# receiver.net
KiCad netlist of a schematic drawn in EAGLE
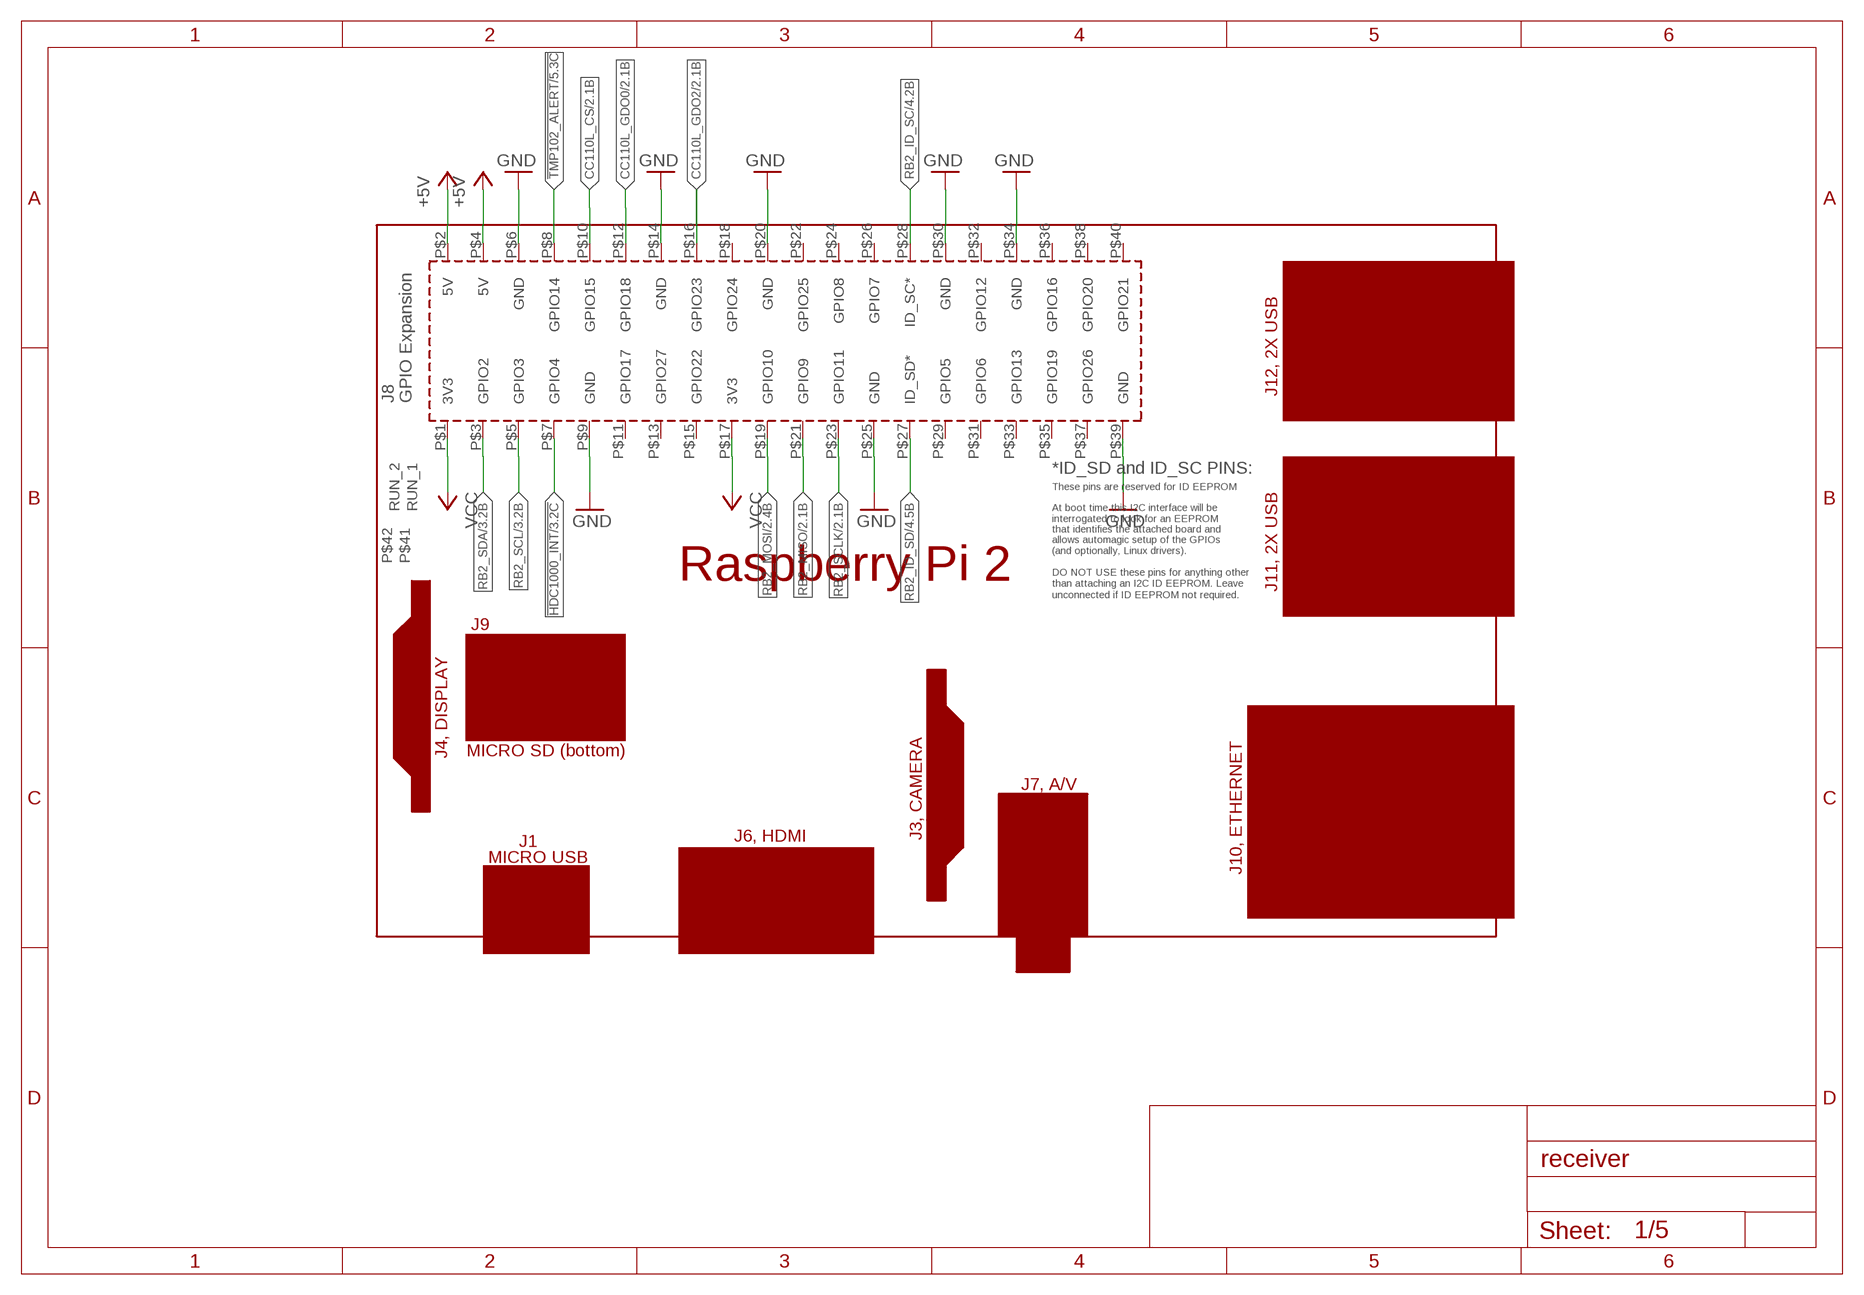
[diagram p0: schematic, sheet 1]
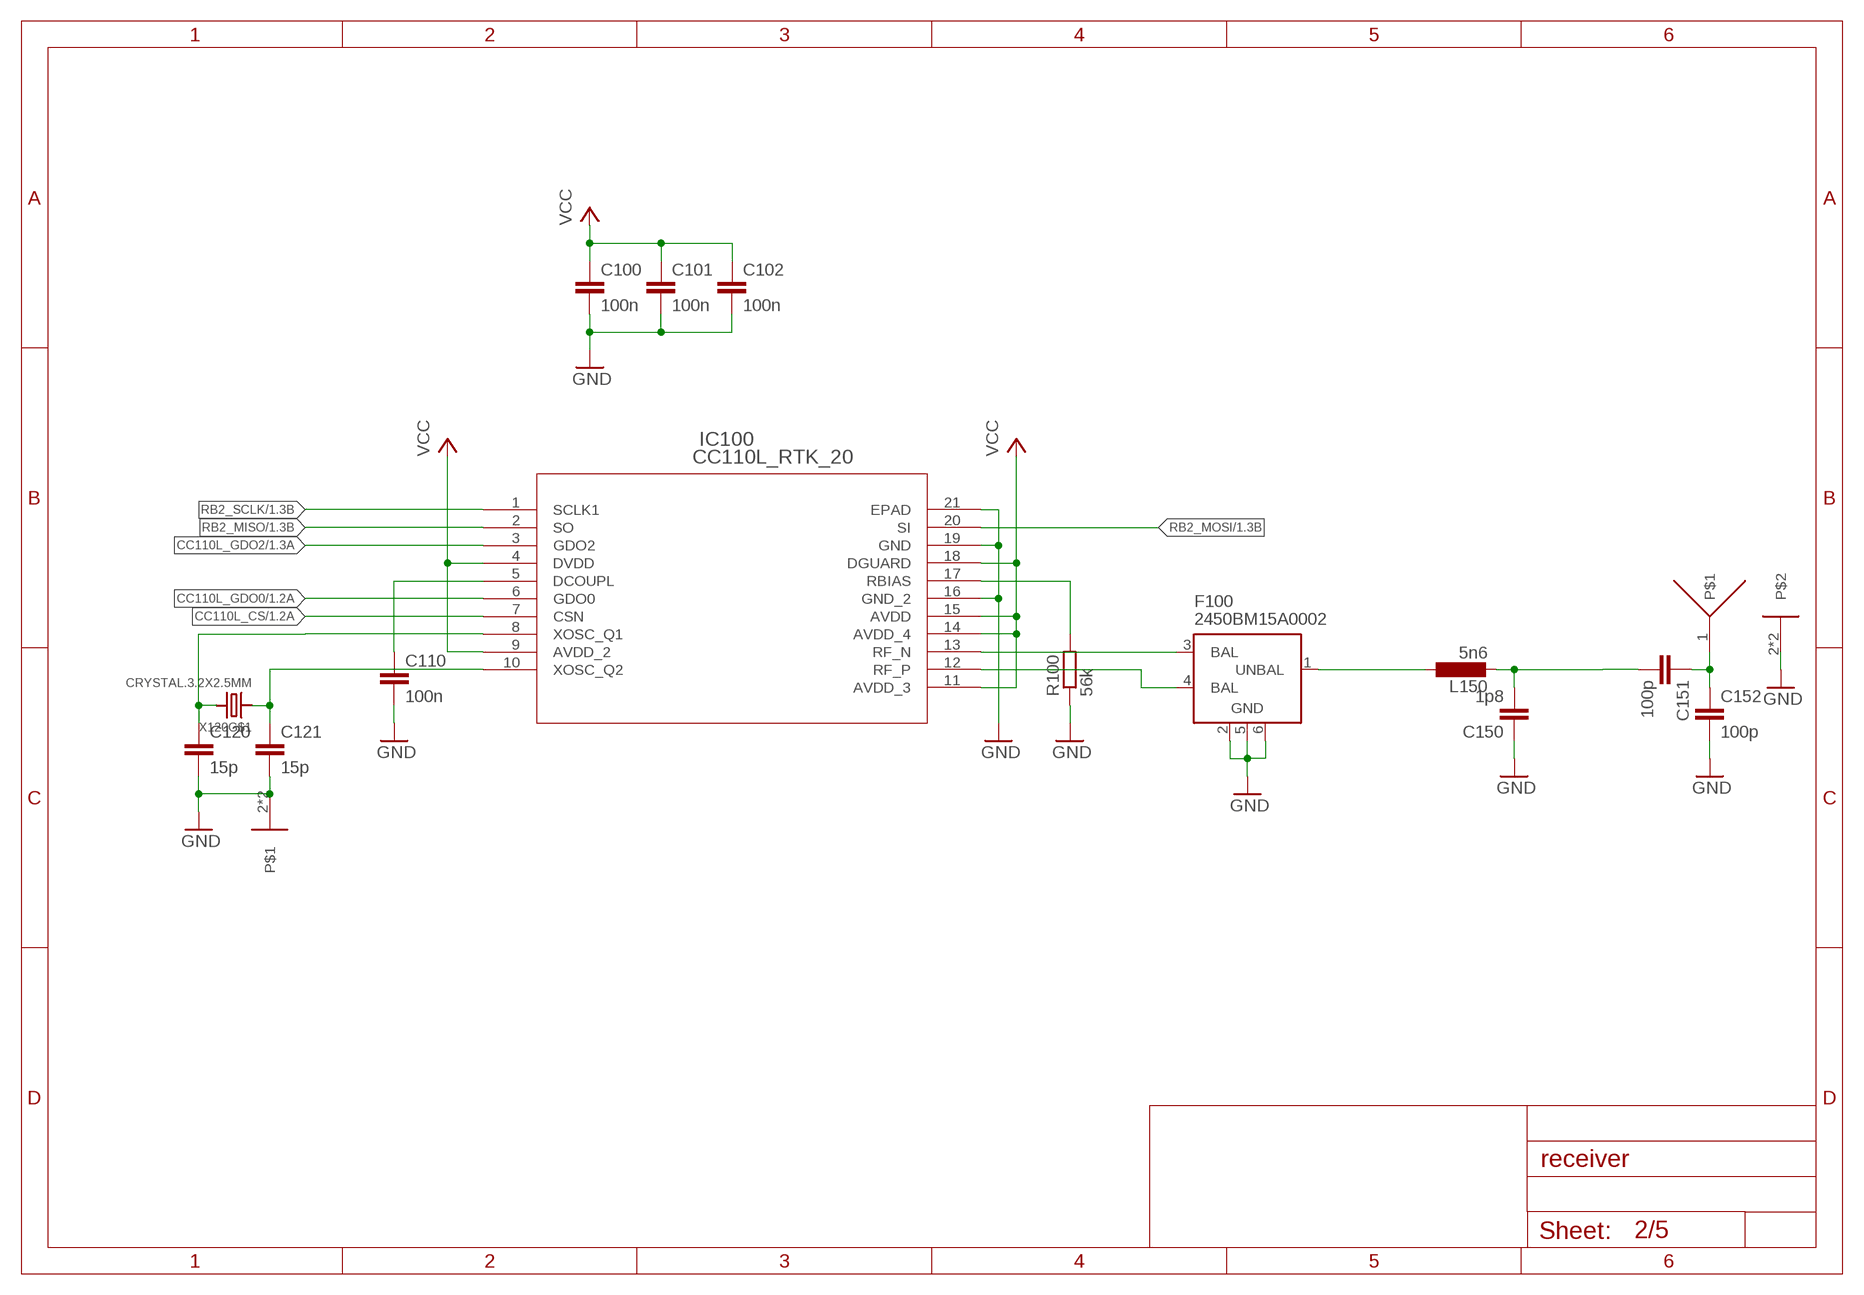
[diagram p1: schematic, sheet 2]
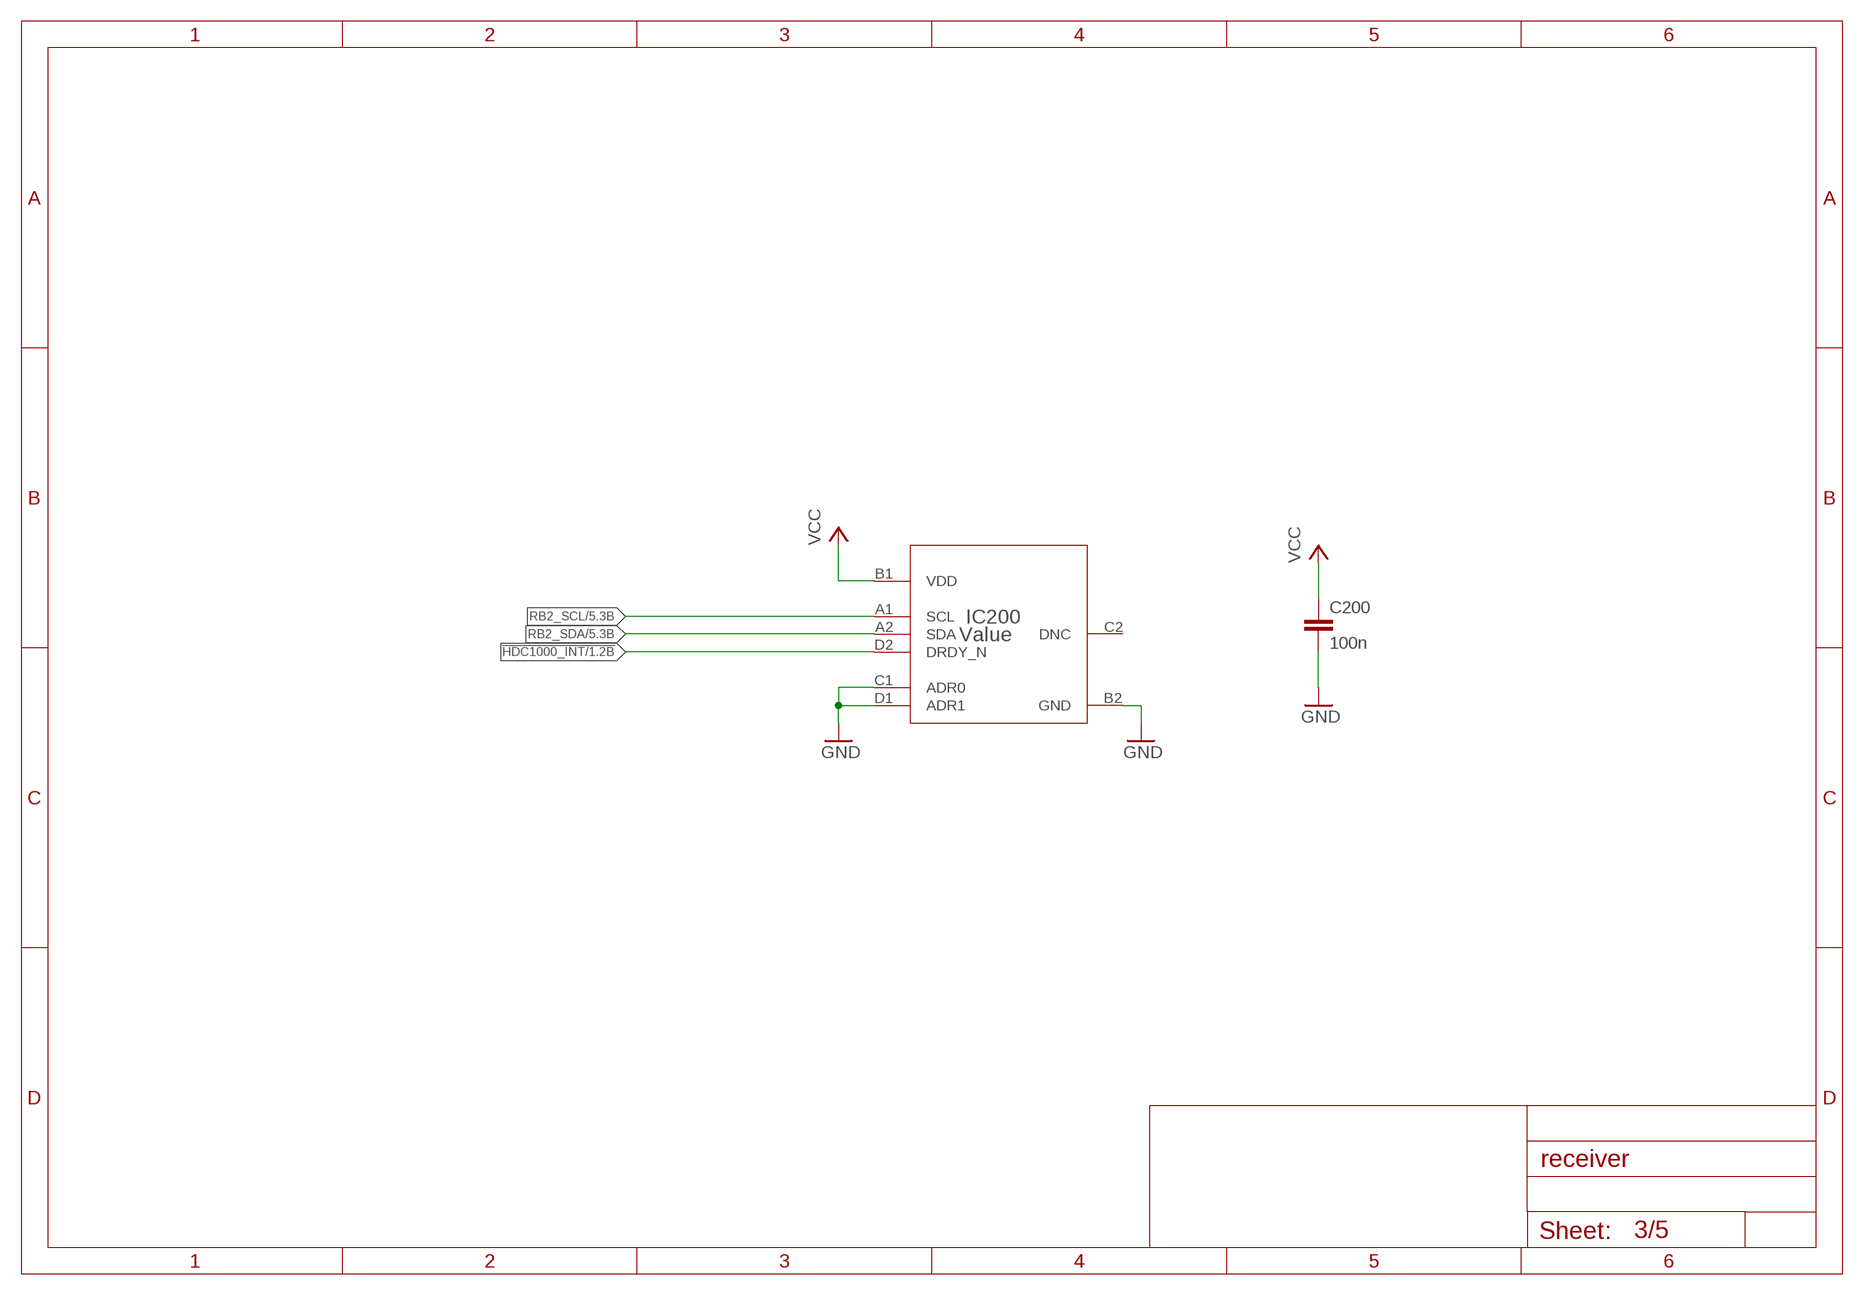
[diagram p2: schematic, sheet 3]
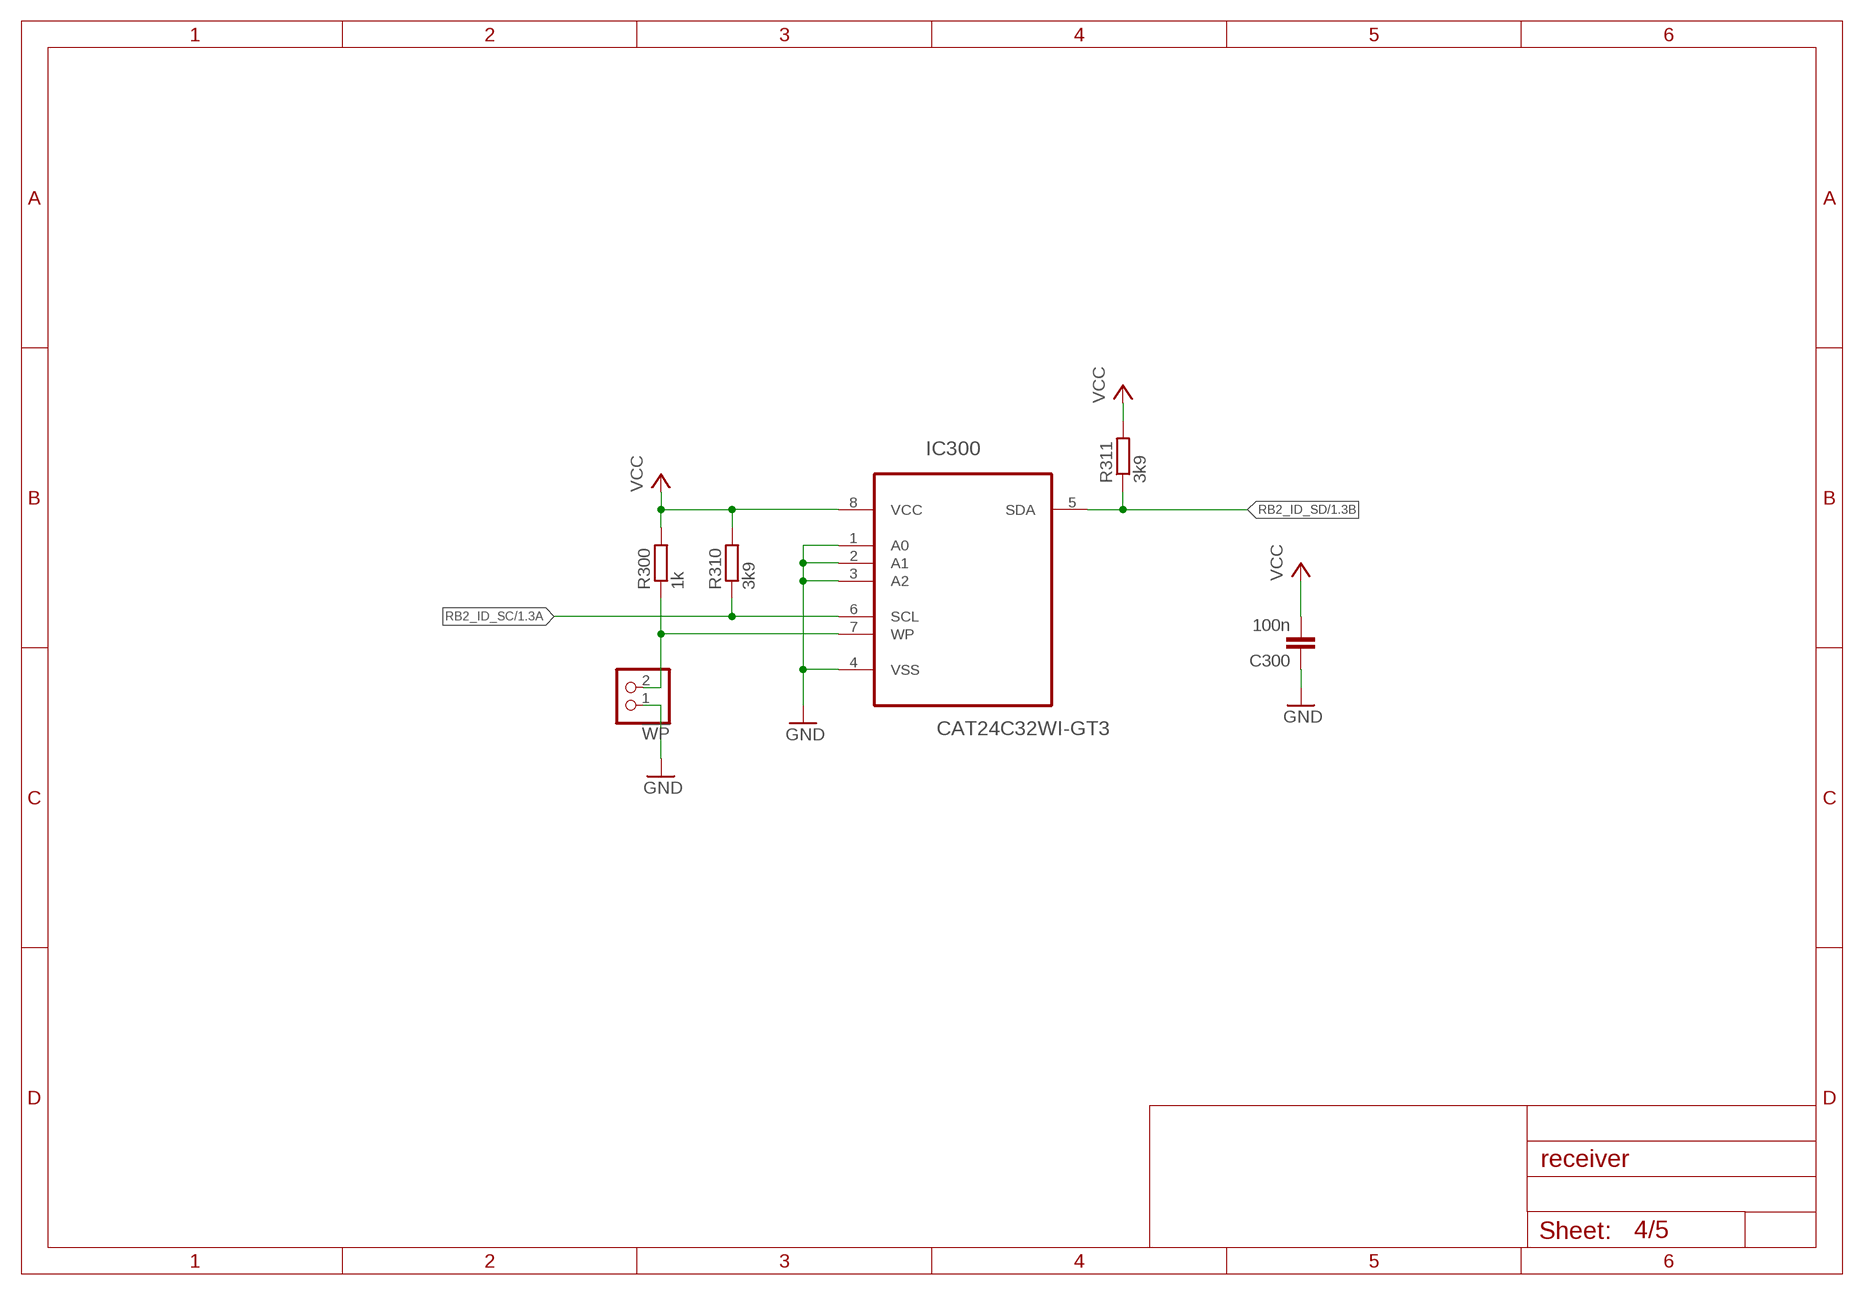
[diagram p3: schematic, sheet 4]
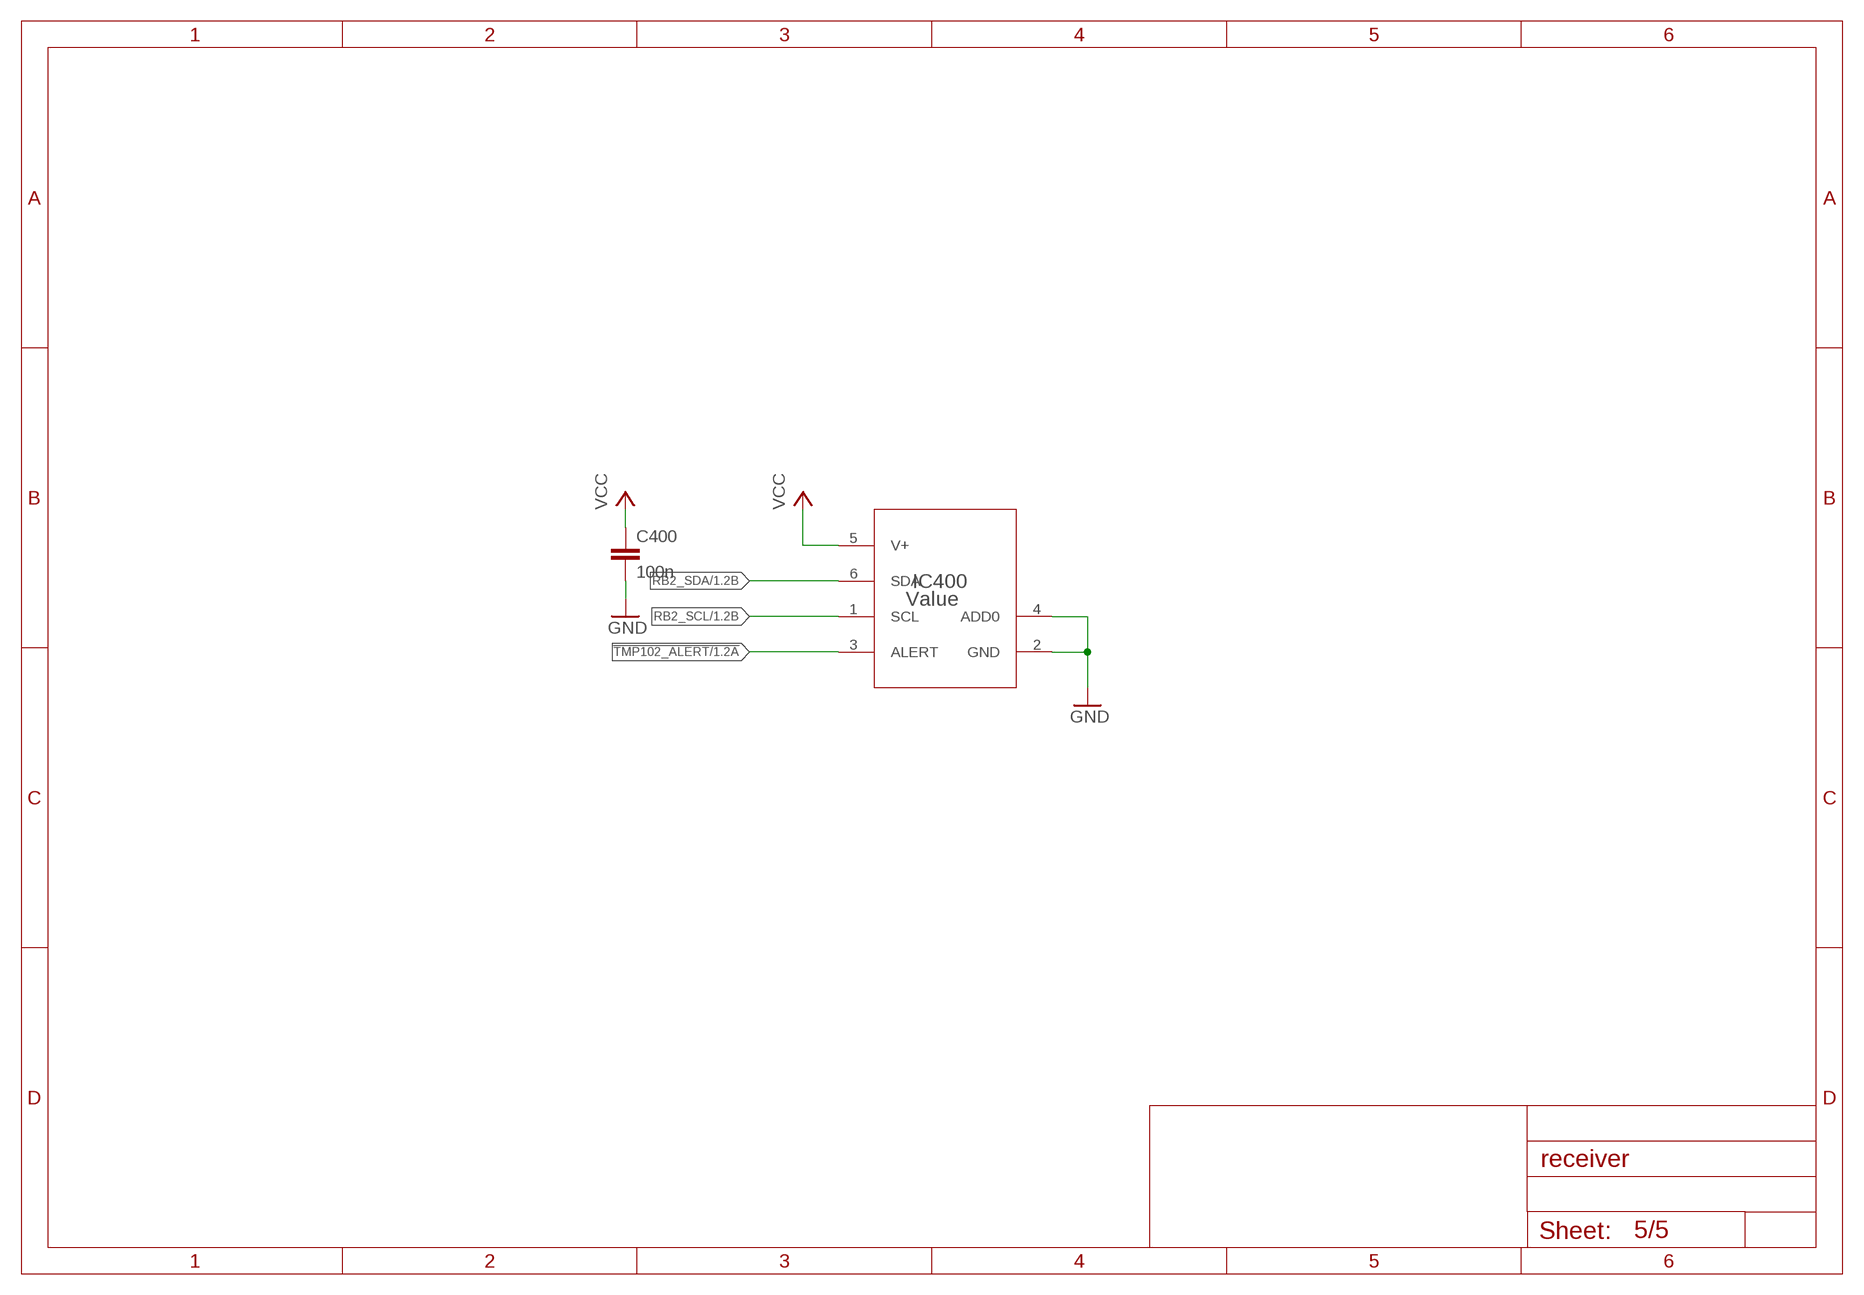
[diagram p4: schematic, sheet 5]

(export (version "E")
  (design (tool "Eeschema 10.0.6"))
  (components
    (comp (ref "C200")
      (value "100n")
      (footprint "eagle-import:C0603")
      (libsource (lib "eagle-import") (part "C-EUC0603"))
    )
    (comp (ref "IC200")
      (value "Value")
      (footprint "eagle-import:YPA0008AGAE")
      (fields
        (field (name "ALTERNATEPARTNUMBER") "HDC1000YPAT")
        (field (name "MANUFACTURER") "Texas Instruments")
        (field (name "PARTNUMBER") "HDC1000YPAR")
      )
      (libsource (lib "eagle-import") (part "HDC1000YPAR"))
    )
    (comp (ref "C100")
      (value "100n")
      (footprint "eagle-import:C0603")
      (libsource (lib "eagle-import") (part "C-EUC0603"))
    )
    (comp (ref "C101")
      (value "100n")
      (footprint "eagle-import:C0603")
      (libsource (lib "eagle-import") (part "C-EUC0603"))
    )
    (comp (ref "C102")
      (value "100n")
      (footprint "eagle-import:C0603")
      (libsource (lib "eagle-import") (part "C-EUC0603"))
    )
    (comp (ref "C110")
      (value "100n")
      (footprint "eagle-import:C0603")
      (libsource (lib "eagle-import") (part "C-EUC0603"))
    )
    (comp (ref "C120")
      (value "15p")
      (footprint "eagle-import:C0603")
      (libsource (lib "eagle-import") (part "C-EUC0603"))
    )
    (comp (ref "C121")
      (value "15p")
      (footprint "eagle-import:C0603")
      (libsource (lib "eagle-import") (part "C-EUC0603"))
    )
    (comp (ref "C150")
      (value "1p8")
      (footprint "eagle-import:C0603K")
      (libsource (lib "eagle-import") (part "C-EUC0603K"))
    )
    (comp (ref "C151")
      (value "100p")
      (footprint "eagle-import:C0603")
      (libsource (lib "eagle-import") (part "C-EUC0603"))
    )
    (comp (ref "C152")
      (value "100p")
      (footprint "eagle-import:C0603K")
      (libsource (lib "eagle-import") (part "C-EUC0603K"))
    )
    (comp (ref "F100")
      (value "2450BM15A0002")
      (footprint "eagle-import:2450BM15A0002")
      (libsource (lib "eagle-import") (part "2450BM15A0002"))
    )
    (comp (ref "IC100")
      (value "CC110L_RTK_20")
      (footprint "eagle-import:RTK20_2P4X2P4")
      (fields (field (name "GENERIC_PART_NUMBER") "CC110L") (field (name "MANUFACTURER") "Texas Instruments"))
      (libsource (lib "eagle-import") (part "CC110L_RTK_20"))
    )
    (comp (ref "L150")
      (value "5n6")
      (footprint "eagle-import:L2012C")
      (libsource (lib "eagle-import") (part "L-EUL2012C"))
    )
    (comp (ref "R100")
      (value "56k")
      (footprint "eagle-import:R0603")
      (libsource (lib "eagle-import") (part "R-EU_R0603"))
    )
    (comp (ref "U$1")
      (value "ANTENNA868W3013-INV")
      (footprint "eagle-import:W3013-INV")
      (libsource (lib "eagle-import") (part "ANTENNA868W3013-INV"))
    )
    (comp (ref "X120")
      (value "CRYSTAL.3.2X2.5MM")
      (footprint "eagle-import:3.2X2.5MM")
      (libsource (lib "eagle-import") (part "CRYSTAL.3.2X2.5MM"))
    )
    (comp (ref "C400")
      (value "100n")
      (footprint "eagle-import:C0603")
      (libsource (lib "eagle-import") (part "C-EUC0603"))
    )
    (comp (ref "IC400")
      (value "Value")
      (footprint "eagle-import:DRL0006A")
      (fields (field (name "MANUFACTURER") "Texas Instruments") (field (name "PARTNUMBER") "TMP102AQDRLRQ1"))
      (libsource (lib "eagle-import") (part "TMP102AQDRLRQ1"))
    )
    (comp (ref "!WP")
      (value "PINHD-1X2")
      (footprint "eagle-import:1X02")
      (libsource (lib "eagle-import") (part "PINHD-1X2"))
    )
    (comp (ref "C300")
      (value "100n")
      (footprint "eagle-import:C0603")
      (libsource (lib "eagle-import") (part "C-EUC0603"))
    )
    (comp (ref "IC300")
      (value "CAT24C32WI-GT3")
      (footprint "eagle-import:SOIC127P600X175-8N")
      (libsource (lib "eagle-import") (part "CAT24C32WI-GT3"))
    )
    (comp (ref "R300")
      (value "1k")
      (footprint "eagle-import:R0603")
      (libsource (lib "eagle-import") (part "R-EU_R0603"))
    )
    (comp (ref "R310")
      (value "3k9")
      (footprint "eagle-import:R0603")
      (libsource (lib "eagle-import") (part "R-EU_R0603"))
    )
    (comp (ref "R311")
      (value "3k9")
      (footprint "eagle-import:R0603")
      (libsource (lib "eagle-import") (part "R-EU_R0603"))
    )
    (comp (ref "PCB1")
      (value "RPI2")
      (footprint "eagle-import:RPI2")
      (libsource (lib "eagle-import") (part "RPI2"))
    )
  )
  (nets
    (net (code "1") (name "+5V") (class "Default")
      (node (ref "PCB1") (pin "P$2") (pinfunction "5V_P$2") (pintype "bidirectional"))
      (node (ref "PCB1") (pin "P$4") (pinfunction "5V_P$4") (pintype "bidirectional"))
    )
    (net (code "2") (name "CC110L_CS") (class "Default")
      (node (ref "IC100") (pin "7") (pinfunction "CSN_7") (pintype "passive"))
      (node (ref "PCB1") (pin "P$10") (pinfunction "GPIO15_P$10") (pintype "bidirectional"))
    )
    (net (code "3") (name "CC110L_GDO0") (class "Default")
      (node (ref "IC100") (pin "6") (pinfunction "GDO0_6") (pintype "output"))
      (node (ref "PCB1") (pin "P$12") (pinfunction "GPIO18_P$12") (pintype "bidirectional"))
    )
    (net (code "4") (name "CC110L_GDO2") (class "Default")
      (node (ref "IC100") (pin "3") (pinfunction "GDO2_3") (pintype "output"))
      (node (ref "PCB1") (pin "P$16") (pinfunction "GPIO23_P$16") (pintype "bidirectional"))
    )
    (net (code "5") (name "GND") (class "Default")
      (node (ref "!WP") (pin "1") (pinfunction "1_1") (pintype "passive"))
      (node (ref "C100") (pin "2") (pinfunction "2_2") (pintype "passive"))
      (node (ref "C101") (pin "2") (pinfunction "2_2") (pintype "passive"))
      (node (ref "C102") (pin "2") (pinfunction "2_2") (pintype "passive"))
      (node (ref "C110") (pin "2") (pinfunction "2_2") (pintype "passive"))
      (node (ref "C120") (pin "2") (pinfunction "2_2") (pintype "passive"))
      (node (ref "C121") (pin "2") (pinfunction "2_2") (pintype "passive"))
      (node (ref "C150") (pin "1") (pinfunction "1_1") (pintype "passive"))
      (node (ref "C152") (pin "2") (pinfunction "2_2") (pintype "passive"))
      (node (ref "C200") (pin "2") (pinfunction "2_2") (pintype "passive"))
      (node (ref "C300") (pin "1") (pinfunction "1_1") (pintype "passive"))
      (node (ref "C400") (pin "2") (pinfunction "2_2") (pintype "passive"))
      (node (ref "F100") (pin "2") (pinfunction "GND_2") (pintype "passive"))
      (node (ref "F100") (pin "5") (pinfunction "GND_5") (pintype "passive"))
      (node (ref "F100") (pin "6") (pinfunction "GND_6") (pintype "passive"))
      (node (ref "IC100") (pin "16") (pinfunction "GND_2_16") (pintype "power_in"))
      (node (ref "IC100") (pin "19") (pinfunction "GND_19") (pintype "power_in"))
      (node (ref "IC100") (pin "21") (pinfunction "EPAD_21") (pintype "power_in"))
      (node (ref "IC200") (pin "B2") (pinfunction "GND_B2") (pintype "power_in"))
      (node (ref "IC200") (pin "C1") (pinfunction "ADR0_C1") (pintype "input"))
      (node (ref "IC200") (pin "D1") (pinfunction "ADR1_D1") (pintype "input"))
      (node (ref "IC300") (pin "1") (pinfunction "A0_1") (pintype "input"))
      (node (ref "IC300") (pin "2") (pinfunction "A1_2") (pintype "input"))
      (node (ref "IC300") (pin "3") (pinfunction "A2_3") (pintype "input"))
      (node (ref "IC300") (pin "4") (pinfunction "VSS_4") (pintype "passive"))
      (node (ref "IC400") (pin "2") (pinfunction "GND_2") (pintype "power_in"))
      (node (ref "IC400") (pin "4") (pinfunction "ADD0_4") (pintype "input"))
      (node (ref "PCB1") (pin "P$14") (pinfunction "GND_P$14") (pintype "bidirectional"))
      (node (ref "PCB1") (pin "P$20") (pinfunction "GND_P$20") (pintype "bidirectional"))
      (node (ref "PCB1") (pin "P$25") (pinfunction "GND_P$25") (pintype "bidirectional"))
      (node (ref "PCB1") (pin "P$30") (pinfunction "GND_P$30") (pintype "bidirectional"))
      (node (ref "PCB1") (pin "P$34") (pinfunction "GND_P$34") (pintype "bidirectional"))
      (node (ref "PCB1") (pin "P$39") (pinfunction "GND_P$39") (pintype "bidirectional"))
      (node (ref "PCB1") (pin "P$6") (pinfunction "GND_P$6") (pintype "bidirectional"))
      (node (ref "PCB1") (pin "P$9") (pinfunction "GND_P$9") (pintype "bidirectional"))
      (node (ref "R100") (pin "1") (pinfunction "1_1") (pintype "passive"))
      (node (ref "U$1") (pin "2") (pinfunction "P$2_2") (pintype "bidirectional"))
      (node (ref "U$1") (pin "3") (pinfunction "P$2_3") (pintype "bidirectional"))
      (node (ref "X120") (pin "2") (pinfunction "P$1_2") (pintype "bidirectional"))
      (node (ref "X120") (pin "4") (pinfunction "P$1_4") (pintype "bidirectional"))
    )
    (net (code "6") (name "Net-(C150-Pad2)") (class "Default")
      (node (ref "C150") (pin "2") (pinfunction "2_2") (pintype "passive"))
      (node (ref "C151") (pin "2") (pinfunction "2_2") (pintype "passive"))
      (node (ref "L150") (pin "2") (pinfunction "2_2") (pintype "passive"))
    )
    (net (code "7") (name "Net-(F100-UNBAL)") (class "Default")
      (node (ref "F100") (pin "1") (pinfunction "UNBAL_1") (pintype "passive"))
      (node (ref "L150") (pin "1") (pinfunction "1_1") (pintype "passive"))
    )
    (net (code "8") (name "Net-(IC100-DCOUPL)") (class "Default")
      (node (ref "C110") (pin "1") (pinfunction "1_1") (pintype "passive"))
      (node (ref "IC100") (pin "5") (pinfunction "DCOUPL_5") (pintype "passive"))
    )
    (net (code "9") (name "Net-(IC100-RBIAS)") (class "Default")
      (node (ref "IC100") (pin "17") (pinfunction "RBIAS_17") (pintype "passive"))
      (node (ref "R100") (pin "2") (pinfunction "2_2") (pintype "passive"))
    )
    (net (code "10") (name "Net-(IC100-RF_N)") (class "Default")
      (node (ref "F100") (pin "3") (pinfunction "BAL_3") (pintype "passive"))
      (node (ref "IC100") (pin "13") (pinfunction "RF_N_13") (pintype "passive"))
    )
    (net (code "11") (name "Net-(IC100-RF_P)") (class "Default")
      (node (ref "F100") (pin "4") (pinfunction "BAL_4") (pintype "passive"))
      (node (ref "IC100") (pin "12") (pinfunction "RF_P_12") (pintype "passive"))
    )
    (net (code "12") (name "Net-(IC100-XOSC_Q1)") (class "Default")
      (node (ref "C120") (pin "1") (pinfunction "1_1") (pintype "passive"))
      (node (ref "IC100") (pin "8") (pinfunction "XOSC_Q1_8") (pintype "passive"))
      (node (ref "X120") (pin "3") (pinfunction "2_3") (pintype "passive"))
    )
    (net (code "13") (name "Net-(IC100-XOSC_Q2)") (class "Default")
      (node (ref "C121") (pin "1") (pinfunction "1_1") (pintype "passive"))
      (node (ref "IC100") (pin "10") (pinfunction "XOSC_Q2_10") (pintype "passive"))
      (node (ref "X120") (pin "1") (pinfunction "1_1") (pintype "passive"))
    )
    (net (code "14") (name "Net-(IC300-WP)") (class "Default")
      (node (ref "!WP") (pin "2") (pinfunction "2_2") (pintype "passive"))
      (node (ref "IC300") (pin "7") (pinfunction "WP_7") (pintype "input"))
      (node (ref "R300") (pin "1") (pinfunction "1_1") (pintype "passive"))
    )
    (net (code "15") (name "Net-(U$1-P$1)") (class "Default")
      (node (ref "C151") (pin "1") (pinfunction "1_1") (pintype "passive"))
      (node (ref "C152") (pin "1") (pinfunction "1_1") (pintype "passive"))
      (node (ref "U$1") (pin "1") (pinfunction "P$1_1") (pintype "bidirectional"))
    )
    (net (code "16") (name "RB2_ID_SC") (class "Default")
      (node (ref "IC300") (pin "6") (pinfunction "SCL_6") (pintype "input"))
      (node (ref "PCB1") (pin "P$28") (pinfunction "ID_SC*_P$28") (pintype "bidirectional"))
      (node (ref "R310") (pin "1") (pinfunction "1_1") (pintype "passive"))
    )
    (net (code "17") (name "RB2_ID_SD") (class "Default")
      (node (ref "IC300") (pin "5") (pinfunction "SDA_5") (pintype "bidirectional"))
      (node (ref "PCB1") (pin "P$27") (pinfunction "ID_SD*_P$27") (pintype "bidirectional"))
      (node (ref "R311") (pin "1") (pinfunction "1_1") (pintype "passive"))
    )
    (net (code "18") (name "RB2_MISO") (class "Default")
      (node (ref "IC100") (pin "2") (pinfunction "SO_2") (pintype "output"))
      (node (ref "PCB1") (pin "P$21") (pinfunction "GPIO9_P$21") (pintype "bidirectional"))
    )
    (net (code "19") (name "RB2_MOSI") (class "Default")
      (node (ref "IC100") (pin "20") (pinfunction "SI_20") (pintype "input"))
      (node (ref "PCB1") (pin "P$19") (pinfunction "GPIO10_P$19") (pintype "bidirectional"))
    )
    (net (code "20") (name "RB2_SCL") (class "Default")
      (node (ref "IC200") (pin "A1") (pinfunction "SCL_A1") (pintype "input"))
      (node (ref "IC400") (pin "1") (pinfunction "SCL_1") (pintype "bidirectional"))
      (node (ref "PCB1") (pin "P$5") (pinfunction "GPIO3_P$5") (pintype "bidirectional"))
    )
    (net (code "21") (name "RB2_SCLK") (class "Default")
      (node (ref "IC100") (pin "1") (pinfunction "SCLK1_1") (pintype "passive"))
      (node (ref "PCB1") (pin "P$23") (pinfunction "GPIO11_P$23") (pintype "bidirectional"))
    )
    (net (code "22") (name "RB2_SDA") (class "Default")
      (node (ref "IC200") (pin "A2") (pinfunction "SDA_A2") (pintype "bidirectional"))
      (node (ref "IC400") (pin "6") (pinfunction "SDA_6") (pintype "bidirectional"))
      (node (ref "PCB1") (pin "P$3") (pinfunction "GPIO2_P$3") (pintype "bidirectional"))
    )
    (net (code "23") (name "VCC") (class "Default")
      (node (ref "C100") (pin "1") (pinfunction "1_1") (pintype "passive"))
      (node (ref "C101") (pin "1") (pinfunction "1_1") (pintype "passive"))
      (node (ref "C102") (pin "1") (pinfunction "1_1") (pintype "passive"))
      (node (ref "C200") (pin "1") (pinfunction "1_1") (pintype "passive"))
      (node (ref "C300") (pin "2") (pinfunction "2_2") (pintype "passive"))
      (node (ref "C400") (pin "1") (pinfunction "1_1") (pintype "passive"))
      (node (ref "IC100") (pin "11") (pinfunction "AVDD_3_11") (pintype "power_in"))
      (node (ref "IC100") (pin "14") (pinfunction "AVDD_4_14") (pintype "power_in"))
      (node (ref "IC100") (pin "15") (pinfunction "AVDD_15") (pintype "power_in"))
      (node (ref "IC100") (pin "18") (pinfunction "DGUARD_18") (pintype "passive"))
      (node (ref "IC100") (pin "4") (pinfunction "DVDD_4") (pintype "power_in"))
      (node (ref "IC100") (pin "9") (pinfunction "AVDD_2_9") (pintype "power_in"))
      (node (ref "IC200") (pin "B1") (pinfunction "VDD_B1") (pintype "power_in"))
      (node (ref "IC300") (pin "8") (pinfunction "VCC_8") (pintype "power_in"))
      (node (ref "IC400") (pin "5") (pinfunction "V+_5") (pintype "power_in"))
      (node (ref "PCB1") (pin "P$1") (pinfunction "3V3_P$1") (pintype "bidirectional"))
      (node (ref "PCB1") (pin "P$17") (pinfunction "3V3_P$17") (pintype "bidirectional"))
      (node (ref "R300") (pin "2") (pinfunction "2_2") (pintype "passive"))
      (node (ref "R310") (pin "2") (pinfunction "2_2") (pintype "passive"))
      (node (ref "R311") (pin "2") (pinfunction "2_2") (pintype "passive"))
    )
    (net (code "24") (name "unconnected-(IC200-DNC-PadC2)") (class "Default")
      (node (ref "IC200") (pin "C2") (pinfunction "DNC_C2") (pintype "passive"))
    )
    (net (code "25") (name "unconnected-(PCB1-GPIO5-PadP$29)") (class "Default")
      (node (ref "PCB1") (pin "P$29") (pinfunction "GPIO5_P$29") (pintype "bidirectional"))
    )
    (net (code "26") (name "unconnected-(PCB1-GPIO6-PadP$31)") (class "Default")
      (node (ref "PCB1") (pin "P$31") (pinfunction "GPIO6_P$31") (pintype "bidirectional"))
    )
    (net (code "27") (name "unconnected-(PCB1-GPIO7-PadP$26)") (class "Default")
      (node (ref "PCB1") (pin "P$26") (pinfunction "GPIO7_P$26") (pintype "bidirectional"))
    )
    (net (code "28") (name "unconnected-(PCB1-GPIO8-PadP$24)") (class "Default")
      (node (ref "PCB1") (pin "P$24") (pinfunction "GPIO8_P$24") (pintype "bidirectional"))
    )
    (net (code "29") (name "unconnected-(PCB1-GPIO12-PadP$32)") (class "Default")
      (node (ref "PCB1") (pin "P$32") (pinfunction "GPIO12_P$32") (pintype "bidirectional"))
    )
    (net (code "30") (name "unconnected-(PCB1-GPIO13-PadP$33)") (class "Default")
      (node (ref "PCB1") (pin "P$33") (pinfunction "GPIO13_P$33") (pintype "bidirectional"))
    )
    (net (code "31") (name "unconnected-(PCB1-GPIO16-PadP$36)") (class "Default")
      (node (ref "PCB1") (pin "P$36") (pinfunction "GPIO16_P$36") (pintype "bidirectional"))
    )
    (net (code "32") (name "unconnected-(PCB1-GPIO17-PadP$11)") (class "Default")
      (node (ref "PCB1") (pin "P$11") (pinfunction "GPIO17_P$11") (pintype "bidirectional"))
    )
    (net (code "33") (name "unconnected-(PCB1-GPIO19-PadP$35)") (class "Default")
      (node (ref "PCB1") (pin "P$35") (pinfunction "GPIO19_P$35") (pintype "bidirectional"))
    )
    (net (code "34") (name "unconnected-(PCB1-GPIO20-PadP$38)") (class "Default")
      (node (ref "PCB1") (pin "P$38") (pinfunction "GPIO20_P$38") (pintype "bidirectional"))
    )
    (net (code "35") (name "unconnected-(PCB1-GPIO21-PadP$40)") (class "Default")
      (node (ref "PCB1") (pin "P$40") (pinfunction "GPIO21_P$40") (pintype "bidirectional"))
    )
    (net (code "36") (name "unconnected-(PCB1-GPIO22-PadP$15)") (class "Default")
      (node (ref "PCB1") (pin "P$15") (pinfunction "GPIO22_P$15") (pintype "bidirectional"))
    )
    (net (code "37") (name "unconnected-(PCB1-GPIO24-PadP$18)") (class "Default")
      (node (ref "PCB1") (pin "P$18") (pinfunction "GPIO24_P$18") (pintype "bidirectional"))
    )
    (net (code "38") (name "unconnected-(PCB1-GPIO25-PadP$22)") (class "Default")
      (node (ref "PCB1") (pin "P$22") (pinfunction "GPIO25_P$22") (pintype "bidirectional"))
    )
    (net (code "39") (name "unconnected-(PCB1-GPIO26-PadP$37)") (class "Default")
      (node (ref "PCB1") (pin "P$37") (pinfunction "GPIO26_P$37") (pintype "bidirectional"))
    )
    (net (code "40") (name "unconnected-(PCB1-GPIO27-PadP$13)") (class "Default")
      (node (ref "PCB1") (pin "P$13") (pinfunction "GPIO27_P$13") (pintype "bidirectional"))
    )
    (net (code "41") (name "unconnected-(PCB1-RUN_1-PadP$41)") (class "Default")
      (node (ref "PCB1") (pin "P$41") (pinfunction "RUN_1_P$41") (pintype "bidirectional"))
    )
    (net (code "42") (name "unconnected-(PCB1-RUN_2-PadP$42)") (class "Default")
      (node (ref "PCB1") (pin "P$42") (pinfunction "RUN_2_P$42") (pintype "bidirectional"))
    )
    (net (code "43") (name "~{HDC1000_INT}") (class "Default")
      (node (ref "IC200") (pin "D2") (pinfunction "DRDY_N_D2") (pintype "input"))
      (node (ref "PCB1") (pin "P$7") (pinfunction "GPIO4_P$7") (pintype "bidirectional"))
    )
    (net (code "44") (name "~{TMP102_ALERT}") (class "Default")
      (node (ref "IC400") (pin "3") (pinfunction "ALERT_3") (pintype "output"))
      (node (ref "PCB1") (pin "P$8") (pinfunction "GPIO14_P$8") (pintype "bidirectional"))
    )
  )
)
